# Mixmaker_schematic.net
KiCad netlist of a schematic drawn in EAGLE
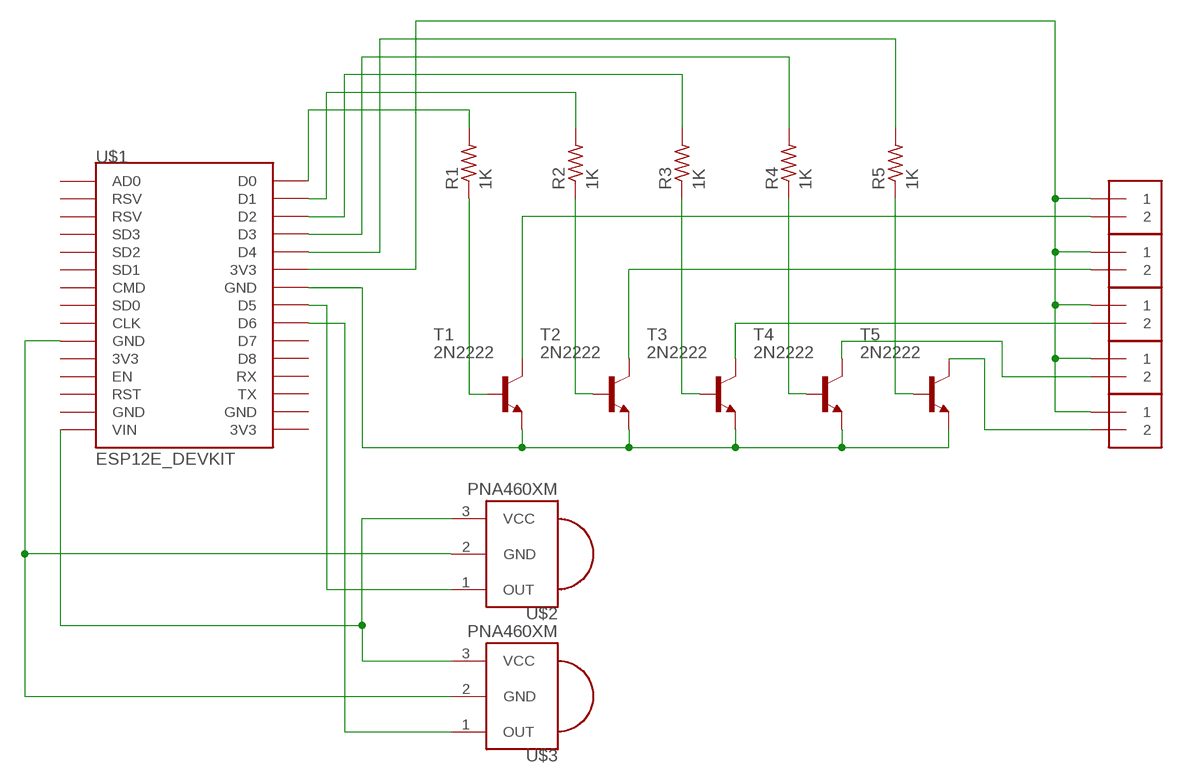
[diagram p0: schematic, sheet 1]

(export (version "E")
  (design (tool "Eeschema 10.0.6"))
  (components
    (comp (ref "J1")
      (value "1X2-3.5MM")
      (footprint "eagle-import:1X2-3.5MM")
      (libsource (lib "eagle-import") (part "1X2-3.5MM"))
    )
    (comp (ref "J2")
      (value "1X2-3.5MM")
      (footprint "eagle-import:1X2-3.5MM")
      (libsource (lib "eagle-import") (part "1X2-3.5MM"))
    )
    (comp (ref "J3")
      (value "1X2-3.5MM")
      (footprint "eagle-import:1X2-3.5MM")
      (libsource (lib "eagle-import") (part "1X2-3.5MM"))
    )
    (comp (ref "J4")
      (value "1X2-3.5MM")
      (footprint "eagle-import:1X2-3.5MM")
      (libsource (lib "eagle-import") (part "1X2-3.5MM"))
    )
    (comp (ref "J5")
      (value "1X2-3.5MM")
      (footprint "eagle-import:1X2-3.5MM")
      (libsource (lib "eagle-import") (part "1X2-3.5MM"))
    )
    (comp (ref "R1")
      (value "1K")
      (footprint "eagle-import:0204_7")
      (libsource (lib "eagle-import") (part "R-US_0204/7"))
    )
    (comp (ref "R2")
      (value "1K")
      (footprint "eagle-import:0204_7")
      (libsource (lib "eagle-import") (part "R-US_0204/7"))
    )
    (comp (ref "R3")
      (value "1K")
      (footprint "eagle-import:0204_7")
      (libsource (lib "eagle-import") (part "R-US_0204/7"))
    )
    (comp (ref "R4")
      (value "1K")
      (footprint "eagle-import:0204_7")
      (libsource (lib "eagle-import") (part "R-US_0204/7"))
    )
    (comp (ref "R5")
      (value "1K")
      (footprint "eagle-import:0204_7")
      (libsource (lib "eagle-import") (part "R-US_0204/7"))
    )
    (comp (ref "T1")
      (value "2N2222")
      (footprint "eagle-import:TO92-EBC-OVAL")
      (libsource (lib "eagle-import") (part "2N2222"))
    )
    (comp (ref "T2")
      (value "2N2222")
      (footprint "eagle-import:TO92-EBC-OVAL")
      (libsource (lib "eagle-import") (part "2N2222"))
    )
    (comp (ref "T3")
      (value "2N2222")
      (footprint "eagle-import:TO92-EBC-OVAL")
      (libsource (lib "eagle-import") (part "2N2222"))
    )
    (comp (ref "T4")
      (value "2N2222")
      (footprint "eagle-import:TO92-EBC-OVAL")
      (libsource (lib "eagle-import") (part "2N2222"))
    )
    (comp (ref "T5")
      (value "2N2222")
      (footprint "eagle-import:TO92-EBC-OVAL")
      (libsource (lib "eagle-import") (part "2N2222"))
    )
    (comp (ref "U$1")
      (value "ESP12E_DEVKIT")
      (footprint "eagle-import:ESP12E_DEVKIT")
      (libsource (lib "eagle-import") (part "ESP12E_DEVKIT"))
    )
    (comp (ref "U$2")
      (value "PNA460XM")
      (footprint "eagle-import:PNA460XM")
      (libsource (lib "eagle-import") (part "PNA460XM"))
    )
    (comp (ref "U$3")
      (value "PNA460XM")
      (footprint "eagle-import:PNA460XM")
      (libsource (lib "eagle-import") (part "PNA460XM"))
    )
  )
  (nets
    (net (code "1") (name "Net-(J1-Pad1)") (class "Default")
      (node (ref "J1") (pin "1") (pinfunction "1_1") (pintype "passive"))
      (node (ref "J2") (pin "1") (pinfunction "1_1") (pintype "passive"))
      (node (ref "J3") (pin "1") (pinfunction "1_1") (pintype "passive"))
      (node (ref "J4") (pin "1") (pinfunction "1_1") (pintype "passive"))
      (node (ref "J5") (pin "1") (pinfunction "1_1") (pintype "passive"))
      (node (ref "U$1") (pin "3V3@1") (pinfunction "3V3_3V3@1") (pintype "bidirectional"))
    )
    (net (code "2") (name "Net-(J1-Pad2)") (class "Default")
      (node (ref "J1") (pin "2") (pinfunction "2_2") (pintype "passive"))
      (node (ref "T1") (pin "C") (pinfunction "C_C") (pintype "passive"))
    )
    (net (code "3") (name "Net-(J2-Pad2)") (class "Default")
      (node (ref "J2") (pin "2") (pinfunction "2_2") (pintype "passive"))
      (node (ref "T2") (pin "C") (pinfunction "C_C") (pintype "passive"))
    )
    (net (code "4") (name "Net-(J3-Pad2)") (class "Default")
      (node (ref "J3") (pin "2") (pinfunction "2_2") (pintype "passive"))
      (node (ref "T3") (pin "C") (pinfunction "C_C") (pintype "passive"))
    )
    (net (code "5") (name "Net-(J4-Pad2)") (class "Default")
      (node (ref "J4") (pin "2") (pinfunction "2_2") (pintype "passive"))
      (node (ref "T4") (pin "C") (pinfunction "C_C") (pintype "passive"))
    )
    (net (code "6") (name "Net-(J5-Pad2)") (class "Default")
      (node (ref "J5") (pin "2") (pinfunction "2_2") (pintype "passive"))
      (node (ref "T5") (pin "C") (pinfunction "C_C") (pintype "passive"))
    )
    (net (code "7") (name "Net-(R1-Pad1)") (class "Default")
      (node (ref "R1") (pin "1") (pinfunction "1_1") (pintype "passive"))
      (node (ref "T1") (pin "B") (pinfunction "B_B") (pintype "passive"))
    )
    (net (code "8") (name "Net-(R1-Pad2)") (class "Default")
      (node (ref "R1") (pin "2") (pinfunction "2_2") (pintype "passive"))
      (node (ref "U$1") (pin "D0") (pinfunction "D0_D0") (pintype "bidirectional"))
    )
    (net (code "9") (name "Net-(R2-Pad1)") (class "Default")
      (node (ref "R2") (pin "1") (pinfunction "1_1") (pintype "passive"))
      (node (ref "T2") (pin "B") (pinfunction "B_B") (pintype "passive"))
    )
    (net (code "10") (name "Net-(R2-Pad2)") (class "Default")
      (node (ref "R2") (pin "2") (pinfunction "2_2") (pintype "passive"))
      (node (ref "U$1") (pin "D1") (pinfunction "D1_D1") (pintype "bidirectional"))
    )
    (net (code "11") (name "Net-(R3-Pad1)") (class "Default")
      (node (ref "R3") (pin "1") (pinfunction "1_1") (pintype "passive"))
      (node (ref "T3") (pin "B") (pinfunction "B_B") (pintype "passive"))
    )
    (net (code "12") (name "Net-(R3-Pad2)") (class "Default")
      (node (ref "R3") (pin "2") (pinfunction "2_2") (pintype "passive"))
      (node (ref "U$1") (pin "D2") (pinfunction "D2_D2") (pintype "bidirectional"))
    )
    (net (code "13") (name "Net-(R4-Pad1)") (class "Default")
      (node (ref "R4") (pin "1") (pinfunction "1_1") (pintype "passive"))
      (node (ref "T4") (pin "B") (pinfunction "B_B") (pintype "passive"))
    )
    (net (code "14") (name "Net-(R4-Pad2)") (class "Default")
      (node (ref "R4") (pin "2") (pinfunction "2_2") (pintype "passive"))
      (node (ref "U$1") (pin "D3") (pinfunction "D3_D3") (pintype "bidirectional"))
    )
    (net (code "15") (name "Net-(R5-Pad1)") (class "Default")
      (node (ref "R5") (pin "1") (pinfunction "1_1") (pintype "passive"))
      (node (ref "T5") (pin "B") (pinfunction "B_B") (pintype "passive"))
    )
    (net (code "16") (name "Net-(R5-Pad2)") (class "Default")
      (node (ref "R5") (pin "2") (pinfunction "2_2") (pintype "passive"))
      (node (ref "U$1") (pin "D4") (pinfunction "D4_D4") (pintype "bidirectional"))
    )
    (net (code "17") (name "Net-(T1-PadE)") (class "Default")
      (node (ref "T1") (pin "E") (pinfunction "E_E") (pintype "passive"))
      (node (ref "T2") (pin "E") (pinfunction "E_E") (pintype "passive"))
      (node (ref "T3") (pin "E") (pinfunction "E_E") (pintype "passive"))
      (node (ref "T4") (pin "E") (pinfunction "E_E") (pintype "passive"))
      (node (ref "T5") (pin "E") (pinfunction "E_E") (pintype "passive"))
      (node (ref "U$1") (pin "GND@2") (pinfunction "GND_GND@2") (pintype "bidirectional"))
    )
    (net (code "18") (name "Net-(U$2-GND)") (class "Default")
      (node (ref "U$1") (pin "GND@0") (pinfunction "GND_GND@0") (pintype "bidirectional"))
      (node (ref "U$2") (pin "2") (pinfunction "GND_2") (pintype "power_in"))
      (node (ref "U$3") (pin "2") (pinfunction "GND_2") (pintype "power_in"))
    )
    (net (code "19") (name "Net-(U$2-OUT)") (class "Default")
      (node (ref "U$1") (pin "D5") (pinfunction "D5_D5") (pintype "bidirectional"))
      (node (ref "U$2") (pin "1") (pinfunction "OUT_1") (pintype "output"))
    )
    (net (code "20") (name "Net-(U$2-VCC)") (class "Default")
      (node (ref "U$1") (pin "VIN") (pinfunction "VIN_VIN") (pintype "bidirectional"))
      (node (ref "U$2") (pin "3") (pinfunction "VCC_3") (pintype "power_in"))
      (node (ref "U$3") (pin "3") (pinfunction "VCC_3") (pintype "power_in"))
    )
    (net (code "21") (name "Net-(U$3-OUT)") (class "Default")
      (node (ref "U$1") (pin "D6") (pinfunction "D6_D6") (pintype "bidirectional"))
      (node (ref "U$3") (pin "1") (pinfunction "OUT_1") (pintype "output"))
    )
    (net (code "22") (name "unconnected-(U$1-3V3-Pad3V3@0)") (class "Default")
      (node (ref "U$1") (pin "3V3@0") (pinfunction "3V3_3V3@0") (pintype "bidirectional"))
    )
    (net (code "23") (name "unconnected-(U$1-3V3-Pad3V3@2)") (class "Default")
      (node (ref "U$1") (pin "3V3@2") (pinfunction "3V3_3V3@2") (pintype "bidirectional"))
    )
    (net (code "24") (name "unconnected-(U$1-GND-PadGND@1)") (class "Default")
      (node (ref "U$1") (pin "GND@1") (pinfunction "GND_GND@1") (pintype "bidirectional"))
    )
    (net (code "25") (name "unconnected-(U$1-GND-PadGND@3)") (class "Default")
      (node (ref "U$1") (pin "GND@3") (pinfunction "GND_GND@3") (pintype "bidirectional"))
    )
    (net (code "26") (name "unconnected-(U$1-PadAD0)") (class "Default")
      (node (ref "U$1") (pin "AD0") (pinfunction "AD0_AD0") (pintype "bidirectional"))
    )
    (net (code "27") (name "unconnected-(U$1-PadCLK)") (class "Default")
      (node (ref "U$1") (pin "CLK") (pinfunction "CLK_CLK") (pintype "bidirectional"))
    )
    (net (code "28") (name "unconnected-(U$1-PadCMD)") (class "Default")
      (node (ref "U$1") (pin "CMD") (pinfunction "CMD_CMD") (pintype "bidirectional"))
    )
    (net (code "29") (name "unconnected-(U$1-PadD7)") (class "Default")
      (node (ref "U$1") (pin "D7") (pinfunction "D7_D7") (pintype "bidirectional"))
    )
    (net (code "30") (name "unconnected-(U$1-PadD8)") (class "Default")
      (node (ref "U$1") (pin "D8") (pinfunction "D8_D8") (pintype "bidirectional"))
    )
    (net (code "31") (name "unconnected-(U$1-PadEN)") (class "Default")
      (node (ref "U$1") (pin "EN") (pinfunction "EN_EN") (pintype "bidirectional"))
    )
    (net (code "32") (name "unconnected-(U$1-PadRST)") (class "Default")
      (node (ref "U$1") (pin "RST") (pinfunction "RST_RST") (pintype "bidirectional"))
    )
    (net (code "33") (name "unconnected-(U$1-PadRX)") (class "Default")
      (node (ref "U$1") (pin "RX") (pinfunction "RX_RX") (pintype "bidirectional"))
    )
    (net (code "34") (name "unconnected-(U$1-PadSD0)") (class "Default")
      (node (ref "U$1") (pin "SD0") (pinfunction "SD0_SD0") (pintype "bidirectional"))
    )
    (net (code "35") (name "unconnected-(U$1-PadSD1)") (class "Default")
      (node (ref "U$1") (pin "SD1") (pinfunction "SD1_SD1") (pintype "bidirectional"))
    )
    (net (code "36") (name "unconnected-(U$1-PadSD2)") (class "Default")
      (node (ref "U$1") (pin "SD2") (pinfunction "SD2_SD2") (pintype "bidirectional"))
    )
    (net (code "37") (name "unconnected-(U$1-PadSD3)") (class "Default")
      (node (ref "U$1") (pin "SD3") (pinfunction "SD3_SD3") (pintype "bidirectional"))
    )
    (net (code "38") (name "unconnected-(U$1-PadTX)") (class "Default")
      (node (ref "U$1") (pin "TX") (pinfunction "TX_TX") (pintype "bidirectional"))
    )
    (net (code "39") (name "unconnected-(U$1-RSV-PadRSV@0)") (class "Default")
      (node (ref "U$1") (pin "RSV@0") (pinfunction "RSV_RSV@0") (pintype "bidirectional"))
    )
    (net (code "40") (name "unconnected-(U$1-RSV-PadRSV@1)") (class "Default")
      (node (ref "U$1") (pin "RSV@1") (pinfunction "RSV_RSV@1") (pintype "bidirectional"))
    )
  )
)
